# mainBoard.net
KiCad netlist of a schematic drawn in EAGLE
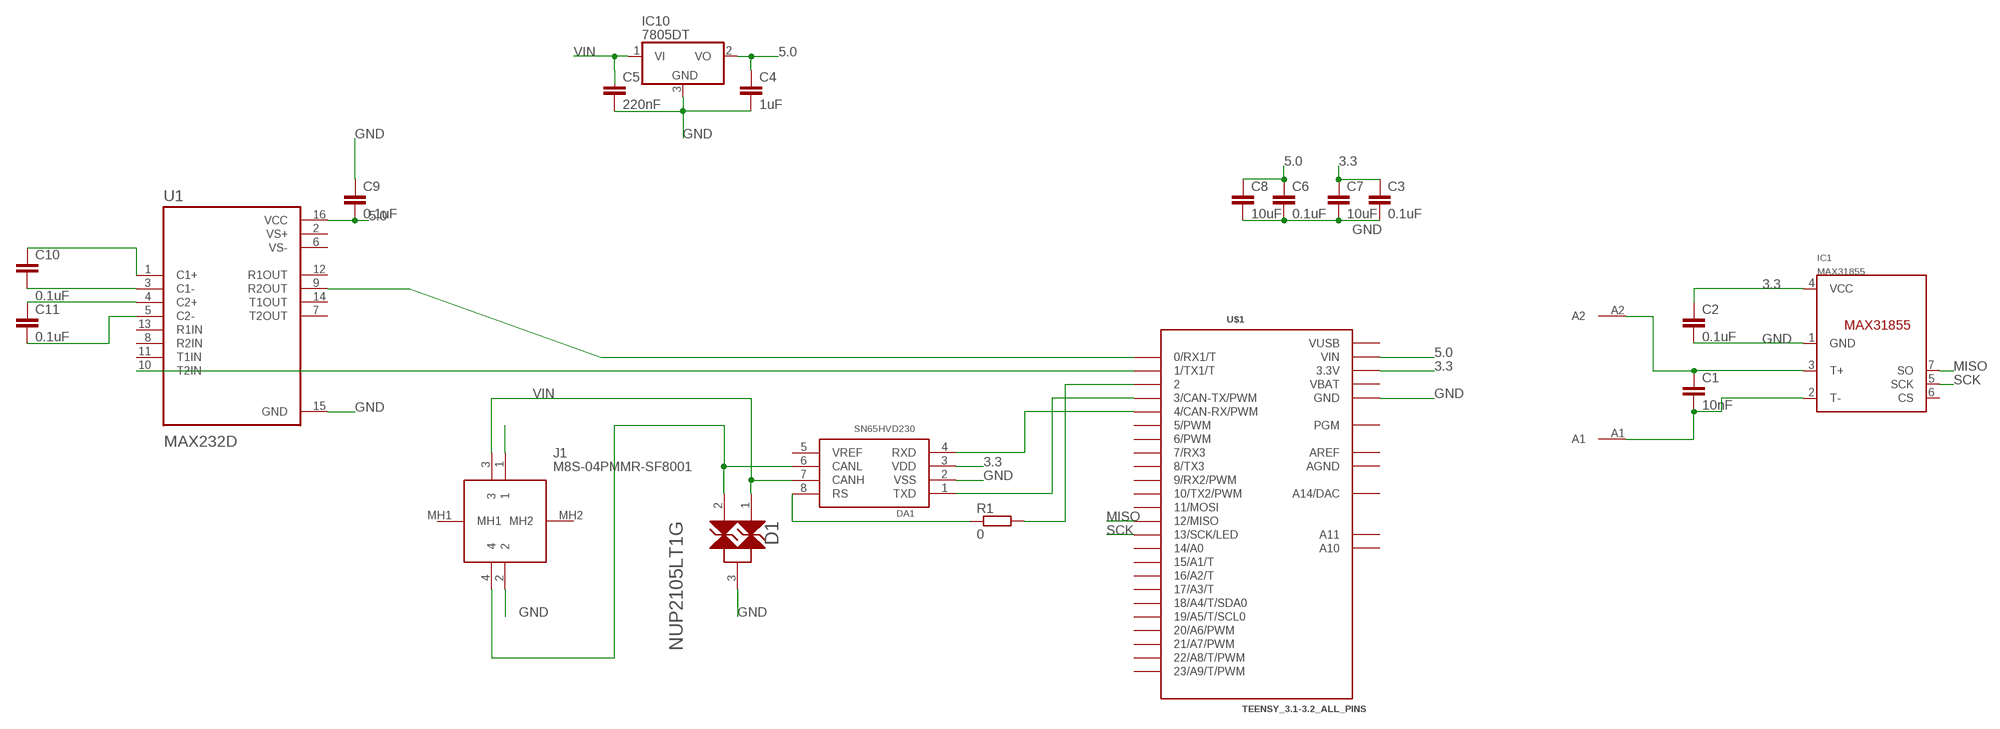
[diagram p0: schematic, sheet 1]

(export (version "E")
  (design (tool "Eeschema 10.0.6"))
  (components
    (comp (ref "C1")
      (value "10nF")
      (footprint "eagle-import:C0805")
      (libsource (lib "eagle-import") (part "C-EUC0805"))
    )
    (comp (ref "C2")
      (value "0.1uF")
      (footprint "eagle-import:C0805")
      (libsource (lib "eagle-import") (part "C-EUC0805"))
    )
    (comp (ref "C3")
      (value "0.1uF")
      (footprint "eagle-import:C0805")
      (libsource (lib "eagle-import") (part "C-EUC0805"))
    )
    (comp (ref "C4")
      (value "1uF")
      (footprint "eagle-import:C0805")
      (libsource (lib "eagle-import") (part "C-EUC0805"))
    )
    (comp (ref "C5")
      (value "220nF")
      (footprint "eagle-import:C0805")
      (libsource (lib "eagle-import") (part "C-EUC0805"))
    )
    (comp (ref "C6")
      (value "0.1uF")
      (footprint "eagle-import:C0805")
      (libsource (lib "eagle-import") (part "C-EUC0805"))
    )
    (comp (ref "C7")
      (value "10uF")
      (footprint "eagle-import:C0805")
      (libsource (lib "eagle-import") (part "C-EUC0805"))
    )
    (comp (ref "C8")
      (value "10uF")
      (footprint "eagle-import:C0805")
      (libsource (lib "eagle-import") (part "C-EUC0805"))
    )
    (comp (ref "C9")
      (value "0.1uF")
      (footprint "eagle-import:C0805")
      (libsource (lib "eagle-import") (part "C-EUC0805"))
    )
    (comp (ref "C10")
      (value "0.1uF")
      (footprint "eagle-import:C0805")
      (libsource (lib "eagle-import") (part "C-EUC0805"))
    )
    (comp (ref "C11")
      (value "0.1uF")
      (footprint "eagle-import:C0805")
      (libsource (lib "eagle-import") (part "C-EUC0805"))
    )
    (comp (ref "D1")
      (value "ON_SEMICONDUCTOR_NUP2105LT1GON_SEMICONDUCTOR_NUP2105LT1G_0_0")
      (footprint "eagle-import:ON_SEMICONDUCTOR_NUP2105LT1G_0")
      (fields (field (name "MF") "On Semiconductor") (field (name "MPN") "NUP2105LT1G"))
      (libsource (lib "eagle-import") (part "ON_SEMICONDUCTOR_NUP2105LT1GON_SEMICONDUCTOR_NUP2105LT1G_0_0"))
    )
    (comp (ref "DA1")
      (value "SN65HVD230")
      (footprint "eagle-import:SO08")
      (libsource (lib "eagle-import") (part "SN65HVD230"))
    )
    (comp (ref "IC1")
      (value "MAX31855")
      (footprint "eagle-import:SOIC8")
      (libsource (lib "eagle-import") (part "MAX31855"))
    )
    (comp (ref "IC10")
      (value "7805DT")
      (footprint "eagle-import:TO252")
      (libsource (lib "eagle-import") (part "78DT05"))
    )
    (comp (ref "J1")
      (value "M8S-04PMMR-SF8001")
      (footprint "eagle-import:M8S04PMMRSF8001")
      (fields (field (name "MOUSER_PART_NUMBER") "523-M8S04PMMRSF8001"))
      (libsource (lib "eagle-import") (part "M8S-04PMMR-SF8001"))
    )
    (comp (ref "R1")
      (value "0")
      (footprint "eagle-import:R0805")
      (libsource (lib "eagle-import") (part "R-EU_R0805"))
    )
    (comp (ref "U$1")
      (value "TEENSY_3.1-3.2_ALL_PINS")
      (footprint "eagle-import:TEENSY_3.0-3.2&LC_ALL_PINS")
      (libsource (lib "eagle-import") (part "TEENSY_3.1-3.2_ALL_PINS"))
    )
    (comp (ref "U$2")
      (value "PCC-SMD")
      (footprint "eagle-import:PCC-SMD")
      (libsource (lib "eagle-import") (part "PCC-SMD"))
    )
    (comp (ref "U1")
      (value "MAX232D")
      (footprint "eagle-import:SOIC127P600X175-16N")
      (fields (field (name "MF") "Texas Instruments"))
      (libsource (lib "eagle-import") (part "MAX232D"))
    )
  )
  (nets
    (net (code "1") (name "/3.3") (class "Default")
      (node (ref "C2") (pin "1") (pinfunction "1_1") (pintype "passive"))
      (node (ref "C3") (pin "1") (pinfunction "1_1") (pintype "passive"))
      (node (ref "C7") (pin "1") (pinfunction "1_1") (pintype "passive"))
      (node (ref "DA1") (pin "3") (pinfunction "VDD_3") (pintype "power_in"))
      (node (ref "IC1") (pin "4") (pinfunction "VCC_4") (pintype "power_in"))
      (node (ref "U$1") (pin "3.3V") (pinfunction "3.3V_3.3V") (pintype "power_in"))
      (node (ref "U$1") (pin "3.3V1") (pinfunction "3.3V_3.3V1") (pintype "power_in"))
    )
    (net (code "2") (name "/5.0") (class "Default")
      (node (ref "C4") (pin "1") (pinfunction "1_1") (pintype "passive"))
      (node (ref "C6") (pin "1") (pinfunction "1_1") (pintype "passive"))
      (node (ref "C8") (pin "1") (pinfunction "1_1") (pintype "passive"))
      (node (ref "C9") (pin "2") (pinfunction "2_2") (pintype "passive"))
      (node (ref "IC10") (pin "2") (pinfunction "VO_2") (pintype "passive"))
      (node (ref "U$1") (pin "VIN") (pinfunction "VIN_VIN") (pintype "power_in"))
      (node (ref "U1") (pin "16") (pinfunction "VCC_16") (pintype "power_in"))
    )
    (net (code "3") (name "/AGND") (class "Default")
      (node (ref "U$1") (pin "AGND") (pinfunction "AGND_AGND") (pintype "power_in"))
    )
    (net (code "4") (name "/AREF") (class "Default")
      (node (ref "U$1") (pin "AREF") (pinfunction "AREF_AREF") (pintype "power_in"))
    )
    (net (code "5") (name "/GND") (class "Default")
      (node (ref "C2") (pin "2") (pinfunction "2_2") (pintype "passive"))
      (node (ref "C3") (pin "2") (pinfunction "2_2") (pintype "passive"))
      (node (ref "C4") (pin "2") (pinfunction "2_2") (pintype "passive"))
      (node (ref "C5") (pin "2") (pinfunction "2_2") (pintype "passive"))
      (node (ref "C6") (pin "2") (pinfunction "2_2") (pintype "passive"))
      (node (ref "C7") (pin "2") (pinfunction "2_2") (pintype "passive"))
      (node (ref "C8") (pin "2") (pinfunction "2_2") (pintype "passive"))
      (node (ref "C9") (pin "1") (pinfunction "1_1") (pintype "passive"))
      (node (ref "D1") (pin "3") (pinfunction "3_K_3") (pintype "passive"))
      (node (ref "DA1") (pin "2") (pinfunction "VSS_2") (pintype "power_in"))
      (node (ref "IC1") (pin "1") (pinfunction "GND_1") (pintype "power_in"))
      (node (ref "IC10") (pin "3") (pinfunction "GND_3") (pintype "passive"))
      (node (ref "J1") (pin "2") (pinfunction "2_2") (pintype "bidirectional"))
      (node (ref "U$1") (pin "GND") (pinfunction "GND_GND") (pintype "power_in"))
      (node (ref "U$1") (pin "GND1") (pinfunction "GND_GND1") (pintype "power_in"))
      (node (ref "U1") (pin "15") (pinfunction "GND_15") (pintype "power_in"))
    )
    (net (code "6") (name "/MISO") (class "Default")
      (node (ref "IC1") (pin "7") (pinfunction "SO_7") (pintype "output"))
      (node (ref "U$1") (pin "12") (pinfunction "12/MISO_12") (pintype "bidirectional"))
    )
    (net (code "7") (name "/SCK") (class "Default")
      (node (ref "IC1") (pin "5") (pinfunction "SCK_5") (pintype "input"))
      (node (ref "U$1") (pin "13") (pinfunction "13/SCK/LED_13") (pintype "bidirectional"))
    )
    (net (code "8") (name "/VBAT") (class "Default")
      (node (ref "U$1") (pin "VBAT") (pinfunction "VBAT_VBAT") (pintype "power_in"))
    )
    (net (code "9") (name "/VIN") (class "Default")
      (node (ref "C5") (pin "1") (pinfunction "1_1") (pintype "passive"))
      (node (ref "IC10") (pin "1") (pinfunction "VI_1") (pintype "input"))
      (node (ref "J1") (pin "1") (pinfunction "1_1") (pintype "bidirectional"))
    )
    (net (code "10") (name "/VS+") (class "Default")
      (node (ref "U1") (pin "2") (pinfunction "VS+_2") (pintype "power_in"))
    )
    (net (code "11") (name "/VS-") (class "Default")
      (node (ref "U1") (pin "6") (pinfunction "VS-_6") (pintype "power_in"))
    )
    (net (code "12") (name "/VUSB") (class "Default")
      (node (ref "U$1") (pin "VUSB") (pinfunction "VUSB_VUSB") (pintype "power_in"))
    )
    (net (code "13") (name "Net-(D1-1_K)") (class "Default")
      (node (ref "D1") (pin "1") (pinfunction "1_K_1") (pintype "passive"))
      (node (ref "DA1") (pin "7") (pinfunction "CANH_7") (pintype "bidirectional"))
      (node (ref "J1") (pin "3") (pinfunction "3_3") (pintype "bidirectional"))
    )
    (net (code "14") (name "Net-(D1-2_K)") (class "Default")
      (node (ref "D1") (pin "2") (pinfunction "2_K_2") (pintype "passive"))
      (node (ref "DA1") (pin "6") (pinfunction "CANL_6") (pintype "bidirectional"))
      (node (ref "J1") (pin "4") (pinfunction "4_4") (pintype "bidirectional"))
    )
    (net (code "15") (name "Net-(DA1-RS)") (class "Default")
      (node (ref "DA1") (pin "8") (pinfunction "RS_8") (pintype "input"))
      (node (ref "R1") (pin "1") (pinfunction "1_1") (pintype "passive"))
    )
    (net (code "16") (name "Net-(DA1-RXD)") (class "Default")
      (node (ref "DA1") (pin "4") (pinfunction "RXD_4") (pintype "output"))
      (node (ref "U$1") (pin "4") (pinfunction "4/CAN-RX/PWM_4") (pintype "bidirectional"))
    )
    (net (code "17") (name "Net-(DA1-TXD)") (class "Default")
      (node (ref "DA1") (pin "1") (pinfunction "TXD_1") (pintype "input"))
      (node (ref "U$1") (pin "3") (pinfunction "3/CAN-TX/PWM_3") (pintype "bidirectional"))
    )
    (net (code "18") (name "Net-(IC1-T+)") (class "Default")
      (node (ref "C1") (pin "1") (pinfunction "1_1") (pintype "passive"))
      (node (ref "IC1") (pin "3") (pinfunction "T+_3") (pintype "input"))
      (node (ref "U$2") (pin "A2") (pinfunction "A2_A2") (pintype "bidirectional"))
    )
    (net (code "19") (name "Net-(IC1-T-)") (class "Default")
      (node (ref "C1") (pin "2") (pinfunction "2_2") (pintype "passive"))
      (node (ref "IC1") (pin "2") (pinfunction "T-_2") (pintype "input"))
      (node (ref "U$2") (pin "A1") (pinfunction "A1_A1") (pintype "bidirectional"))
    )
    (net (code "20") (name "Net-(R1-Pad2)") (class "Default")
      (node (ref "R1") (pin "2") (pinfunction "2_2") (pintype "passive"))
      (node (ref "U$1") (pin "2") (pinfunction "2_2") (pintype "bidirectional"))
    )
    (net (code "21") (name "Net-(U$1-0{slash}RX1{slash}T)") (class "Default")
      (node (ref "U$1") (pin "0") (pinfunction "0/RX1/T_0") (pintype "bidirectional"))
      (node (ref "U1") (pin "9") (pinfunction "R2OUT_9") (pintype "output"))
    )
    (net (code "22") (name "Net-(U$1-1{slash}TX1{slash}T)") (class "Default")
      (node (ref "U$1") (pin "1") (pinfunction "1/TX1/T_1") (pintype "bidirectional"))
      (node (ref "U1") (pin "10") (pinfunction "T2IN_10") (pintype "input"))
    )
    (net (code "23") (name "Net-(U1-C1+)") (class "Default")
      (node (ref "C10") (pin "1") (pinfunction "1_1") (pintype "passive"))
      (node (ref "U1") (pin "1") (pinfunction "C1+_1") (pintype "input"))
    )
    (net (code "24") (name "Net-(U1-C1-)") (class "Default")
      (node (ref "C10") (pin "2") (pinfunction "2_2") (pintype "passive"))
      (node (ref "U1") (pin "3") (pinfunction "C1-_3") (pintype "input"))
    )
    (net (code "25") (name "Net-(U1-C2+)") (class "Default")
      (node (ref "C11") (pin "1") (pinfunction "1_1") (pintype "passive"))
      (node (ref "U1") (pin "4") (pinfunction "C2+_4") (pintype "input"))
    )
    (net (code "26") (name "Net-(U1-C2-)") (class "Default")
      (node (ref "C11") (pin "2") (pinfunction "2_2") (pintype "passive"))
      (node (ref "U1") (pin "5") (pinfunction "C2-_5") (pintype "input"))
    )
    (net (code "27") (name "unconnected-(DA1-VREF-Pad5)") (class "Default")
      (node (ref "DA1") (pin "5") (pinfunction "VREF_5") (pintype "passive"))
    )
    (net (code "28") (name "unconnected-(IC1-CS-Pad6)") (class "Default")
      (node (ref "IC1") (pin "6") (pinfunction "CS_6") (pintype "input"))
    )
    (net (code "29") (name "unconnected-(J1-PadMH1)") (class "Default")
      (node (ref "J1") (pin "MH1") (pinfunction "MH1_MH1") (pintype "bidirectional"))
    )
    (net (code "30") (name "unconnected-(J1-PadMH2)") (class "Default")
      (node (ref "J1") (pin "MH2") (pinfunction "MH2_MH2") (pintype "bidirectional"))
    )
    (net (code "31") (name "unconnected-(U$1-5{slash}PWM-Pad5)") (class "Default")
      (node (ref "U$1") (pin "5") (pinfunction "5/PWM_5") (pintype "bidirectional"))
    )
    (net (code "32") (name "unconnected-(U$1-6{slash}PWM-Pad6)") (class "Default")
      (node (ref "U$1") (pin "6") (pinfunction "6/PWM_6") (pintype "bidirectional"))
    )
    (net (code "33") (name "unconnected-(U$1-7{slash}RX3-Pad7)") (class "Default")
      (node (ref "U$1") (pin "7") (pinfunction "7/RX3_7") (pintype "bidirectional"))
    )
    (net (code "34") (name "unconnected-(U$1-8{slash}TX3-Pad8)") (class "Default")
      (node (ref "U$1") (pin "8") (pinfunction "8/TX3_8") (pintype "bidirectional"))
    )
    (net (code "35") (name "unconnected-(U$1-9{slash}RX2{slash}PWM-Pad9)") (class "Default")
      (node (ref "U$1") (pin "9") (pinfunction "9/RX2/PWM_9") (pintype "bidirectional"))
    )
    (net (code "36") (name "unconnected-(U$1-10{slash}TX2{slash}PWM-Pad10)") (class "Default")
      (node (ref "U$1") (pin "10") (pinfunction "10/TX2/PWM_10") (pintype "bidirectional"))
    )
    (net (code "37") (name "unconnected-(U$1-11{slash}MOSI-Pad11)") (class "Default")
      (node (ref "U$1") (pin "11") (pinfunction "11/MOSI_11") (pintype "bidirectional"))
    )
    (net (code "38") (name "unconnected-(U$1-15{slash}A1{slash}T-Pad15{slash}A1)") (class "Default")
      (node (ref "U$1") (pin "15/A1") (pinfunction "15/A1/T_15/A1") (pintype "bidirectional"))
    )
    (net (code "39") (name "unconnected-(U$1-16{slash}A2{slash}T-Pad16{slash}A2)") (class "Default")
      (node (ref "U$1") (pin "16/A2") (pinfunction "16/A2/T_16/A2") (pintype "bidirectional"))
    )
    (net (code "40") (name "unconnected-(U$1-17{slash}A3{slash}T-Pad17{slash}A3)") (class "Default")
      (node (ref "U$1") (pin "17/A3") (pinfunction "17/A3/T_17/A3") (pintype "bidirectional"))
    )
    (net (code "41") (name "unconnected-(U$1-18{slash}A4{slash}T{slash}SDA0-Pad18{slash}A4)") (class "Default")
      (node (ref "U$1") (pin "18/A4") (pinfunction "18/A4/T/SDA0_18/A4") (pintype "bidirectional"))
    )
    (net (code "42") (name "unconnected-(U$1-19{slash}A5{slash}T{slash}SCL0-Pad19{slash}A5)") (class "Default")
      (node (ref "U$1") (pin "19/A5") (pinfunction "19/A5/T/SCL0_19/A5") (pintype "bidirectional"))
    )
    (net (code "43") (name "unconnected-(U$1-20{slash}A6{slash}PWM-Pad20{slash}A6)") (class "Default")
      (node (ref "U$1") (pin "20/A6") (pinfunction "20/A6/PWM_20/A6") (pintype "bidirectional"))
    )
    (net (code "44") (name "unconnected-(U$1-21{slash}A7{slash}PWM-Pad21{slash}A7)") (class "Default")
      (node (ref "U$1") (pin "21/A7") (pinfunction "21/A7/PWM_21/A7") (pintype "bidirectional"))
    )
    (net (code "45") (name "unconnected-(U$1-22{slash}A8{slash}T{slash}PWM-Pad22{slash}A8)") (class "Default")
      (node (ref "U$1") (pin "22/A8") (pinfunction "22/A8/T/PWM_22/A8") (pintype "bidirectional"))
    )
    (net (code "46") (name "unconnected-(U$1-23{slash}A9{slash}T{slash}PWM-Pad23{slash}A9)") (class "Default")
      (node (ref "U$1") (pin "23/A9") (pinfunction "23/A9/T/PWM_23/A9") (pintype "bidirectional"))
    )
    (net (code "47") (name "unconnected-(U$1-A14{slash}DAC-PadRESET{slash}DAC)") (class "Default")
      (node (ref "U$1") (pin "RESET/DAC") (pinfunction "A14/DAC_RESET/DAC") (pintype "bidirectional"))
    )
    (net (code "48") (name "unconnected-(U$1-Pad14{slash}A0)") (class "Default")
      (node (ref "U$1") (pin "14/A0") (pinfunction "14/A0_14/A0") (pintype "bidirectional"))
    )
    (net (code "49") (name "unconnected-(U$1-PadA10)") (class "Default")
      (node (ref "U$1") (pin "A10") (pinfunction "A10_A10") (pintype "bidirectional"))
    )
    (net (code "50") (name "unconnected-(U$1-PadA11)") (class "Default")
      (node (ref "U$1") (pin "A11") (pinfunction "A11_A11") (pintype "bidirectional"))
    )
    (net (code "51") (name "unconnected-(U$1-PadPGM)") (class "Default")
      (node (ref "U$1") (pin "PGM") (pinfunction "PGM_PGM") (pintype "bidirectional"))
    )
    (net (code "52") (name "unconnected-(U1-R1IN-Pad13)") (class "Default")
      (node (ref "U1") (pin "13") (pinfunction "R1IN_13") (pintype "input"))
    )
    (net (code "53") (name "unconnected-(U1-R1OUT-Pad12)") (class "Default")
      (node (ref "U1") (pin "12") (pinfunction "R1OUT_12") (pintype "output"))
    )
    (net (code "54") (name "unconnected-(U1-R2IN-Pad8)") (class "Default")
      (node (ref "U1") (pin "8") (pinfunction "R2IN_8") (pintype "input"))
    )
    (net (code "55") (name "unconnected-(U1-T1IN-Pad11)") (class "Default")
      (node (ref "U1") (pin "11") (pinfunction "T1IN_11") (pintype "input"))
    )
    (net (code "56") (name "unconnected-(U1-T1OUT-Pad14)") (class "Default")
      (node (ref "U1") (pin "14") (pinfunction "T1OUT_14") (pintype "output"))
    )
    (net (code "57") (name "unconnected-(U1-T2OUT-Pad7)") (class "Default")
      (node (ref "U1") (pin "7") (pinfunction "T2OUT_7") (pintype "output"))
    )
  )
)
